# sensor_35mm.net
KiCad netlist of a schematic drawn in EAGLE
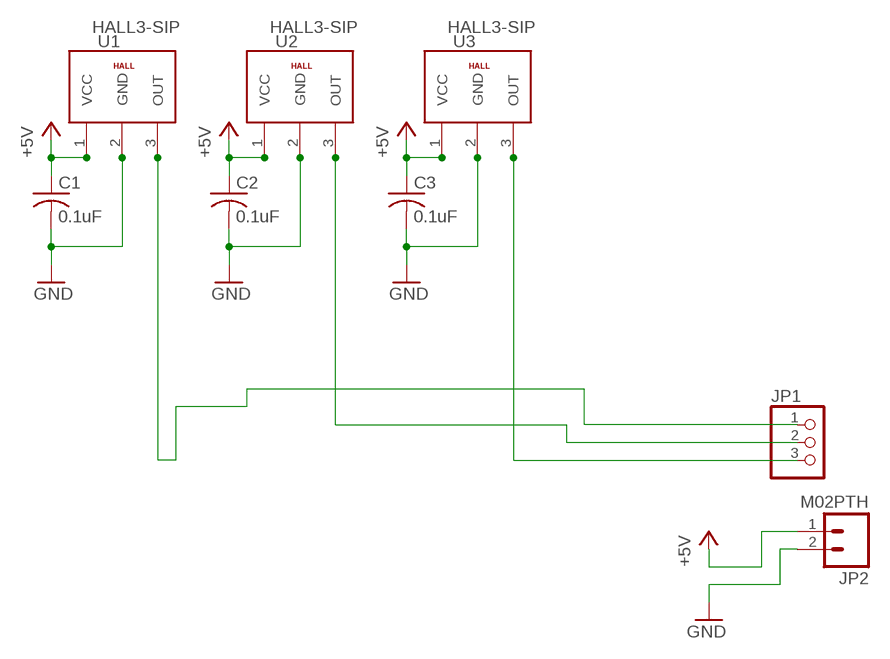
[diagram p0: schematic, sheet 1]

(export (version "E")
  (design (tool "Eeschema 10.0.6"))
  (components
    (comp (ref "C1")
      (value "0.1uF")
      (footprint "eagle-import:C0603")
      (libsource (lib "eagle-import") (part "C-USC0603"))
    )
    (comp (ref "C2")
      (value "0.1uF")
      (footprint "eagle-import:C0603")
      (libsource (lib "eagle-import") (part "C-USC0603"))
    )
    (comp (ref "C3")
      (value "0.1uF")
      (footprint "eagle-import:C0603")
      (libsource (lib "eagle-import") (part "C-USC0603"))
    )
    (comp (ref "JP1")
      (value "PINHD-1X3CB")
      (footprint "eagle-import:1X03-CLEANBIG")
      (libsource (lib "eagle-import") (part "PINHD-1X3CB"))
    )
    (comp (ref "JP2")
      (value "M02PTH")
      (footprint "eagle-import:1X02")
      (libsource (lib "eagle-import") (part "M02PTH"))
    )
    (comp (ref "U1")
      (value "HALL3-SIP")
      (footprint "eagle-import:3PINS1,27")
      (libsource (lib "eagle-import") (part "HALL3-SIP"))
    )
    (comp (ref "U2")
      (value "HALL3-SIP")
      (footprint "eagle-import:3PINS1,27")
      (libsource (lib "eagle-import") (part "HALL3-SIP"))
    )
    (comp (ref "U3")
      (value "HALL3-SIP")
      (footprint "eagle-import:3PINS1,27")
      (libsource (lib "eagle-import") (part "HALL3-SIP"))
    )
  )
  (nets
    (net (code "1") (name "+5V") (class "Default")
      (node (ref "C1") (pin "1") (pinfunction "1_1") (pintype "passive"))
      (node (ref "C2") (pin "1") (pinfunction "1_1") (pintype "passive"))
      (node (ref "C3") (pin "1") (pinfunction "1_1") (pintype "passive"))
      (node (ref "JP2") (pin "1") (pinfunction "1_1") (pintype "passive"))
      (node (ref "U1") (pin "1") (pinfunction "VCC_1") (pintype "bidirectional"))
      (node (ref "U2") (pin "1") (pinfunction "VCC_1") (pintype "bidirectional"))
      (node (ref "U3") (pin "1") (pinfunction "VCC_1") (pintype "bidirectional"))
    )
    (net (code "2") (name "GND") (class "Default")
      (node (ref "C1") (pin "2") (pinfunction "2_2") (pintype "passive"))
      (node (ref "C2") (pin "2") (pinfunction "2_2") (pintype "passive"))
      (node (ref "C3") (pin "2") (pinfunction "2_2") (pintype "passive"))
      (node (ref "JP2") (pin "2") (pinfunction "2_2") (pintype "passive"))
      (node (ref "U1") (pin "2") (pinfunction "GND_2") (pintype "bidirectional"))
      (node (ref "U2") (pin "2") (pinfunction "GND_2") (pintype "bidirectional"))
      (node (ref "U3") (pin "2") (pinfunction "GND_2") (pintype "bidirectional"))
    )
    (net (code "3") (name "Net-(U1-OUT)") (class "Default")
      (node (ref "JP1") (pin "1") (pinfunction "1_1") (pintype "passive"))
      (node (ref "U1") (pin "3") (pinfunction "OUT_3") (pintype "bidirectional"))
    )
    (net (code "4") (name "Net-(U2-OUT)") (class "Default")
      (node (ref "JP1") (pin "2") (pinfunction "2_2") (pintype "passive"))
      (node (ref "U2") (pin "3") (pinfunction "OUT_3") (pintype "bidirectional"))
    )
    (net (code "5") (name "Net-(U3-OUT)") (class "Default")
      (node (ref "JP1") (pin "3") (pinfunction "3_3") (pintype "passive"))
      (node (ref "U3") (pin "3") (pinfunction "OUT_3") (pintype "bidirectional"))
    )
  )
)
